# MCU.net
KiCad netlist of a schematic drawn in Altium Designer
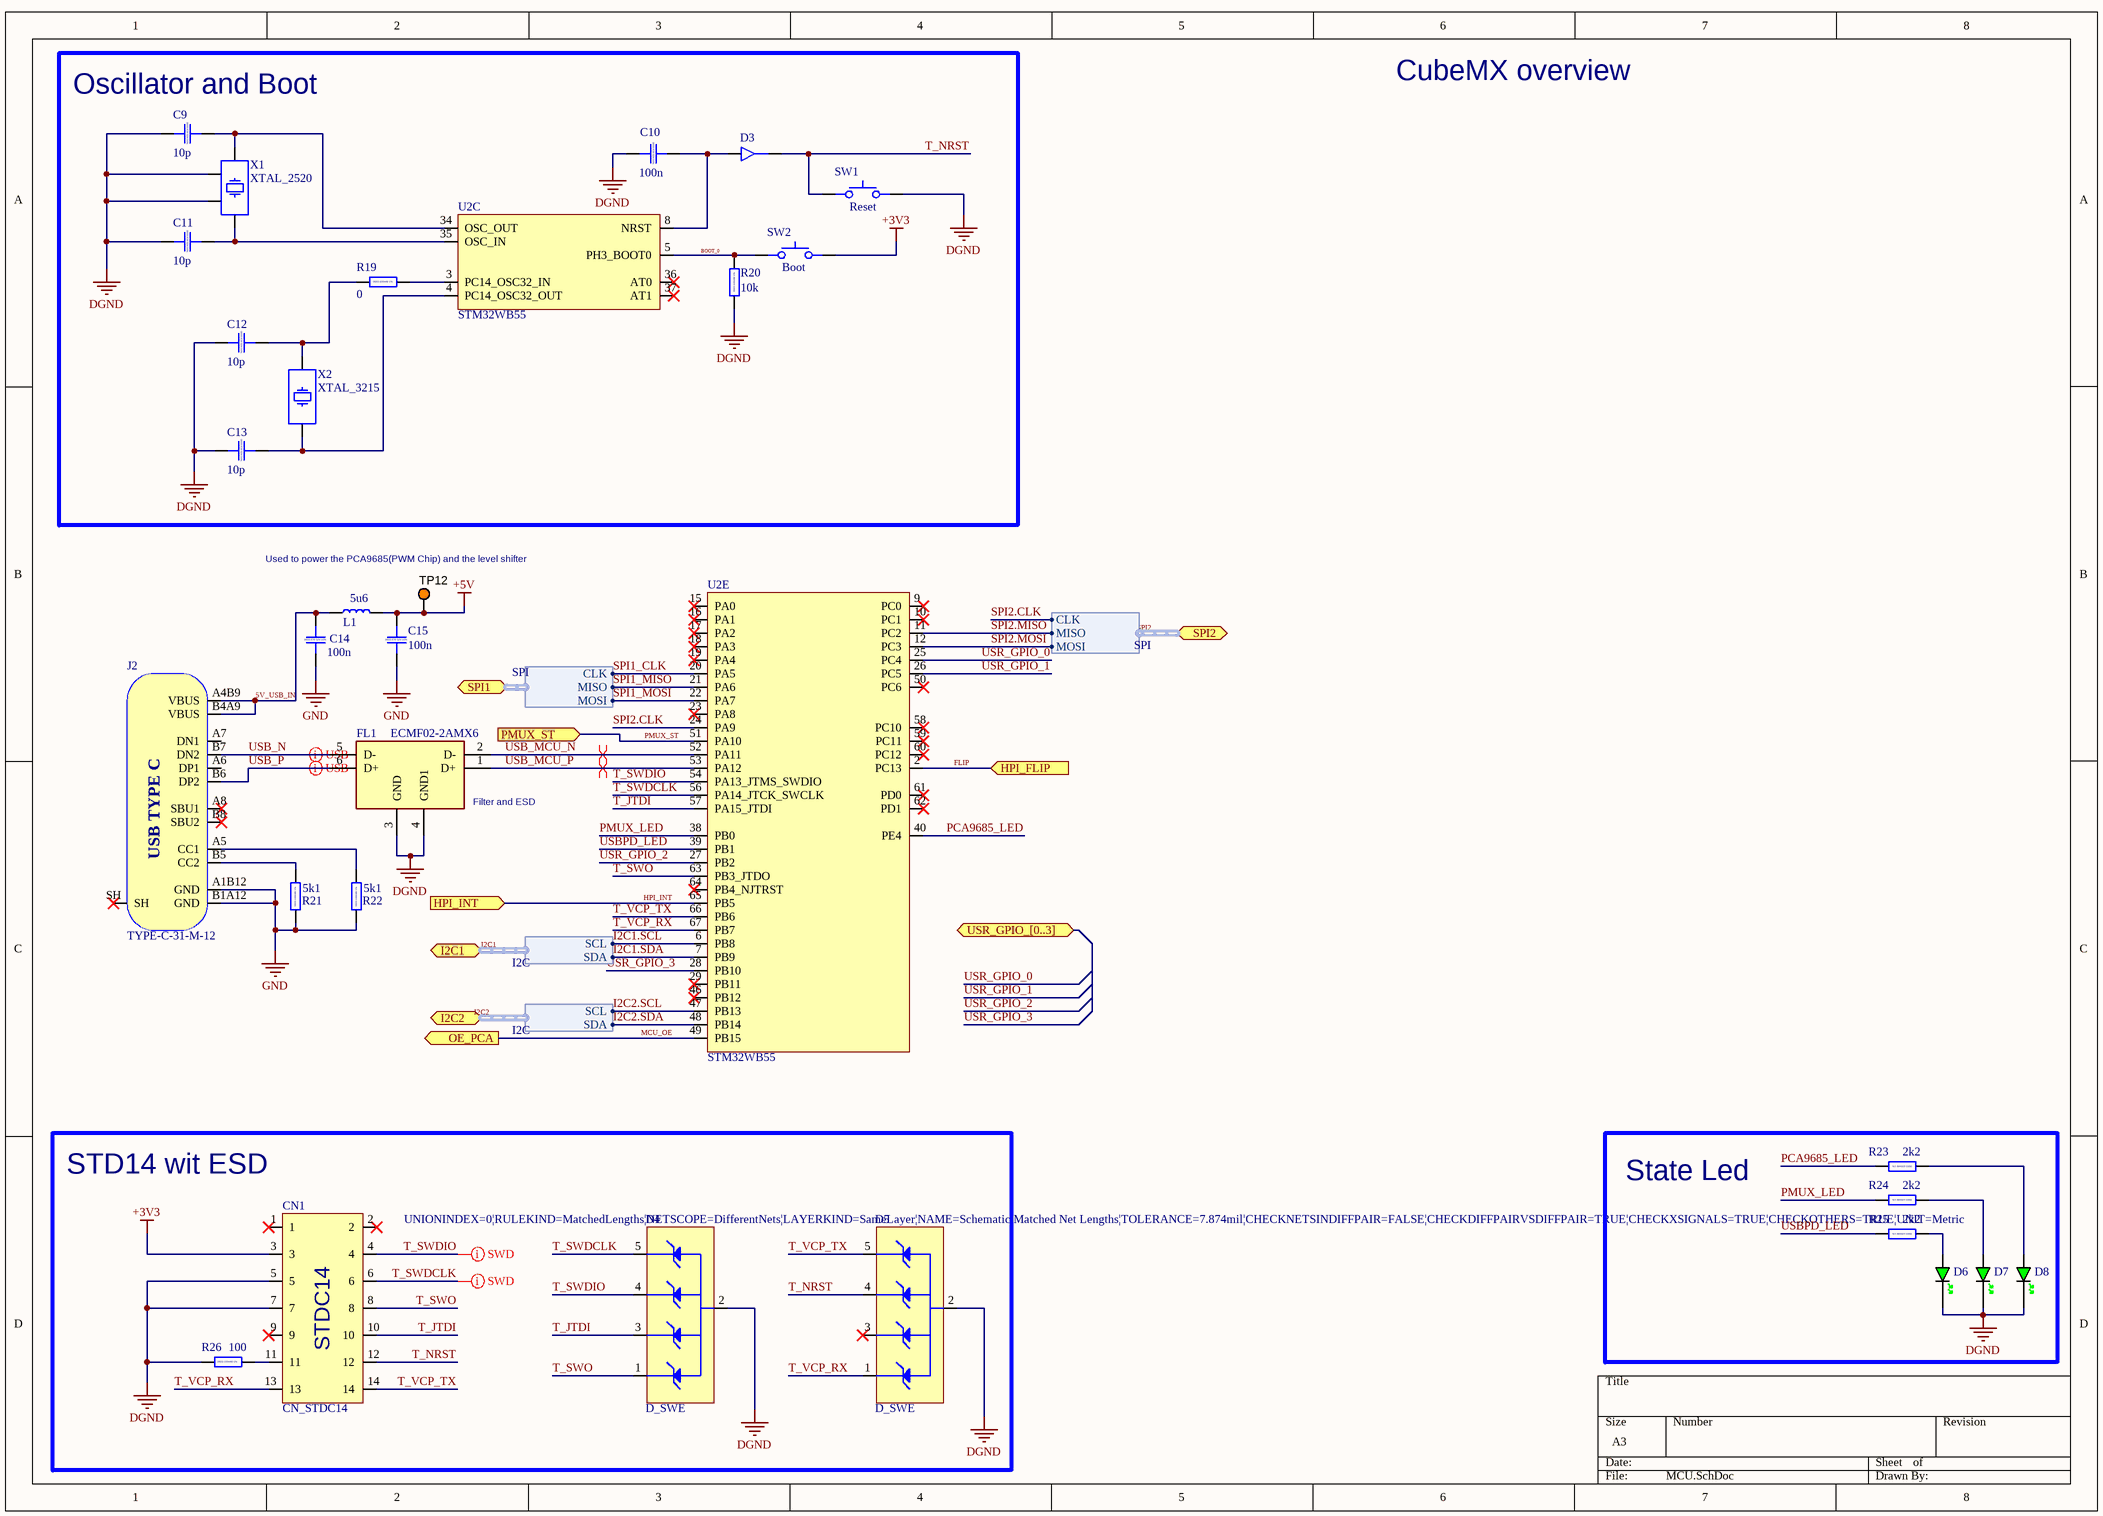
[diagram p0: MCU.SchDoc]

(export (version "E")
  (design (tool "Eeschema 10.0.6"))
  (components
    (comp (ref "C9")
      (value "10p")
      (footprint "CAP_0603")
      (description "Capacitor SMD 0603")
      (fields (field (name "SOURCE") "Schematic-Lib-PhilsLab.SchLib"))
      (libsource (lib "Leonhard Waibl") (part "CAP_EL_NP_5MM"))
    )
    (comp (ref "C10")
      (value "100n")
      (footprint "CAP_0603")
      (description "Capacitor SMD 0603")
      (fields (field (name "SOURCE") "Schematic-Lib-PhilsLab.SchLib"))
      (libsource (lib "Leonhard Waibl") (part "CAP_EL_NP_5MM"))
    )
    (comp (ref "C11")
      (value "10p")
      (footprint "CAP_0603")
      (description "Capacitor SMD 0603")
      (fields (field (name "SOURCE") "Schematic-Lib-PhilsLab.SchLib"))
      (libsource (lib "Leonhard Waibl") (part "CAP_EL_NP_5MM"))
    )
    (comp (ref "C12")
      (value "10p")
      (footprint "CAP_0603")
      (description "Capacitor SMD 0603")
      (fields (field (name "SOURCE") "Schematic-Lib-PhilsLab.SchLib"))
      (libsource (lib "Leonhard Waibl") (part "CAP_EL_NP_5MM"))
    )
    (comp (ref "C13")
      (value "10p")
      (footprint "CAP_0603")
      (description "Capacitor SMD 0603")
      (fields (field (name "SOURCE") "Schematic-Lib-PhilsLab.SchLib"))
      (libsource (lib "Leonhard Waibl") (part "CAP_EL_NP_5MM"))
    )
    (comp (ref "C14")
      (value "100n")
      (footprint "CAP_0603")
      (description "Capacitor SMD 0603")
      (fields (field (name "SOURCE") "Schematic-Lib-PhilsLab.SchLib"))
      (libsource (lib "Leonhard Waibl") (part "CAP_EL_NP_5MM"))
    )
    (comp (ref "C15")
      (value "100n")
      (footprint "CAP_0603")
      (description "Capacitor SMD 0603")
      (fields (field (name "SOURCE") "Schematic-Lib-PhilsLab.SchLib"))
      (libsource (lib "Leonhard Waibl") (part "CAP_EL_NP_5MM"))
    )
    (comp (ref "CN1")
      (value "CN_STDC14")
      (footprint "FTSH-107-01-F-DV-K-P-TR-Footprint-1")
      (libsource (lib "Leonhard Waibl") (part "CN_STDC14"))
    )
    (comp (ref "D3")
      (value "D_SOD_323")
      (footprint "SOD-323")
      (description "Diode SMD SOD-323")
      (fields (field (name "SOURCE") "Schematic-Lib-PhilsLab.SchLib"))
      (libsource (lib "Leonhard Waibl") (part "D_ZENER_SOD_323"))
    )
    (comp (ref "D4")
      (value "D_SWE")
      (footprint "SOT65P210X110-5N")
      (description "ESDALC6V1W5 Trans Voltage Suppressor Diode, 25W, Unidirectional, 4 Element, Silicon")
      (libsource (lib "Leonhard Waibl") (part "ESDALC6V1W5"))
    )
    (comp (ref "D5")
      (value "D_SWE")
      (footprint "SOT65P210X110-5N")
      (description "ESDALC6V1W5 Trans Voltage Suppressor Diode, 25W, Unidirectional, 4 Element, Silicon")
      (libsource (lib "Leonhard Waibl") (part "ESDALC6V1W5"))
    )
    (comp (ref "D6")
      (value "LED_0603_GREEN")
      (footprint "LED_0603_GREEN")
      (description "LED 0603 GREEN SMD")
      (fields (field (name "SOURCE") "Schematic-Lib-PhilsLab.SchLib"))
      (libsource (lib "Leonhard Waibl") (part "LED_0805_GREEN"))
    )
    (comp (ref "D7")
      (value "LED_0603_GREEN")
      (footprint "LED_0603_GREEN")
      (description "LED 0603 GREEN SMD")
      (fields (field (name "SOURCE") "Schematic-Lib-PhilsLab.SchLib"))
      (libsource (lib "Leonhard Waibl") (part "LED_0805_GREEN"))
    )
    (comp (ref "D8")
      (value "LED_0603_GREEN")
      (footprint "LED_0603_GREEN")
      (description "LED 0603 GREEN SMD")
      (fields (field (name "SOURCE") "Schematic-Lib-PhilsLab.SchLib"))
      (libsource (lib "Leonhard Waibl") (part "LED_0805_GREEN"))
    )
    (comp (ref "FL1")
      (value "ECMF02-2AMX6")
      (footprint "FP-QFN-6L-IPC_A")
      (description "Data Line Filter, 2 Function(s), 6 Pin(s), Plastic")
      (libsource (lib "Leonhard Waibl") (part "8feffc7f24acfb857157da90e949b57"))
    )
    (comp (ref "J2")
      (value "TYPE-C-31-M-12")
      (footprint "TYPE-C-31-M-12")
      (description "USB Type C Connector Horizontal SMT")
      (fields
        (field (name "MANUFACTURER") "Koren Hroparts")
        (field (name "SOURCE") "Schematic-Lib-PhilsLab.SchLib")
      )
      (libsource (lib "Leonhard Waibl") (part "TYPE-C-31-M-12"))
    )
    (comp (ref "L1")
      (value "5u6")
      (footprint "IND_0603")
      (description "Inductor SMD 0603")
      (fields (field (name "SOURCE") "Schematic-Lib-PhilsLab.SchLib"))
      (libsource (lib "Leonhard Waibl") (part "ASPI-0630HI-6R8M-T15"))
    )
    (comp (ref "R19")
      (value "0")
      (footprint "RES_0603")
      (description "Resistor 0603 100mW 1%")
      (fields (field (name "SOURCE") "Schematic-Lib-PhilsLab.SchLib"))
      (libsource (lib "Leonhard Waibl") (part "RES_5931"))
    )
    (comp (ref "R20")
      (value "10k")
      (footprint "RES_0603")
      (description "Resistor 0603 100mW 1%")
      (fields (field (name "SOURCE") "Schematic-Lib-PhilsLab.SchLib"))
      (libsource (lib "Leonhard Waibl") (part "RES_5931"))
    )
    (comp (ref "R21")
      (value "5k1")
      (footprint "RES_0603")
      (description "Resistor 0603 100mW 1%")
      (fields (field (name "SOURCE") "Schematic-Lib-PhilsLab.SchLib"))
      (libsource (lib "Leonhard Waibl") (part "RES_5931"))
    )
    (comp (ref "R22")
      (value "5k1")
      (footprint "RES_0603")
      (description "Resistor 0603 100mW 1%")
      (fields (field (name "SOURCE") "Schematic-Lib-PhilsLab.SchLib"))
      (libsource (lib "Leonhard Waibl") (part "RES_5931"))
    )
    (comp (ref "R23")
      (value "2k2")
      (footprint "RES_0603")
      (description "Resistor 0603 100mW 1%")
      (fields (field (name "SOURCE") "Schematic-Lib-PhilsLab.SchLib"))
      (libsource (lib "Leonhard Waibl") (part "RES_5931"))
    )
    (comp (ref "R24")
      (value "2k2")
      (footprint "RES_0603")
      (description "Resistor 0603 100mW 1%")
      (fields (field (name "SOURCE") "Schematic-Lib-PhilsLab.SchLib"))
      (libsource (lib "Leonhard Waibl") (part "RES_5931"))
    )
    (comp (ref "R25")
      (value "2k2")
      (footprint "RES_0603")
      (description "Resistor 0603 100mW 1%")
      (fields (field (name "SOURCE") "Schematic-Lib-PhilsLab.SchLib"))
      (libsource (lib "Leonhard Waibl") (part "RES_5931"))
    )
    (comp (ref "R26")
      (value "100")
      (footprint "RES_0603")
      (description "Resistor 0603 100mW 1%")
      (fields (field (name "SOURCE") "Schematic-Lib-PhilsLab.SchLib"))
      (libsource (lib "Leonhard Waibl") (part "RES_5931"))
    )
    (comp (ref "SW1")
      (value "Reset")
      (footprint "SKRPANE010")
      (description "Tactile Switch SMD SPST")
      (fields
        (field (name "MANUFACTURER PART NUMBER") "SKRPANE010")
        (field (name "MANUFACTURER") "Alps Alpine")
        (field (name "SOURCE") "Schematic-Lib-PhilsLab.SchLib")
      )
      (libsource (lib "Leonhard Waibl") (part "SKRPANE010"))
    )
    (comp (ref "SW2")
      (value "Boot")
      (footprint "SKRPANE010")
      (description "Tactile Switch SMD SPST")
      (fields
        (field (name "MANUFACTURER PART NUMBER") "SKRPANE010")
        (field (name "MANUFACTURER") "Alps Alpine")
        (field (name "SOURCE") "Schematic-Lib-PhilsLab.SchLib")
      )
      (libsource (lib "Leonhard Waibl") (part "SKRPANE010"))
    )
    (comp (ref "TP12")
      (value "5003")
      (footprint "KSTN-5003")
      (description "Test Point, Orange, Height 4.6 mm, Tail Length 3 mm, 1-Pin THD, RoHS")
      (fields (field (name "MANUFACTURER") "Keystone"))
      (libsource (lib "Leonhard Waibl") (part "TESTPOINT_ORANGE"))
    )
    (comp (ref "U2")
      (value "STM32WB55")
      (footprint "QFN40P800X800X100_HS-69N")
      (description "Multiprotocol wireless 32-bit MCU Arm®-based Cortex®-M4")
      (libsource (lib "Leonhard Waibl") (part "STM32WBxx_QFN68"))
    )
    (comp (ref "X1")
      (value "XTAL_2520")
      (footprint "XTAL_2520")
      (description "Crystal SMD 2520")
      (fields (field (name "SOURCE") "Schematic-Lib-PhilsLab.SchLib"))
      (libsource (lib "Leonhard Waibl") (part "TSX-3225_24.0000MF15X-AC"))
    )
    (comp (ref "X2")
      (value "XTAL_3215")
      (footprint "XTAL_3215-2")
      (description "Crystal SMD 3215")
      (fields (field (name "SOURCE") "Schematic-Lib-PhilsLab.SchLib"))
      (libsource (lib "Leonhard Waibl") (part "XTAL_3215"))
    )
  )
  (nets
    (net (code "5") (name "+3V3") (class "Default")
      (node (ref "CN1") (pin "3") (pinfunction "3_3") (pintype "passive"))
      (node (ref "SW2") (pin "34") (pintype "passive"))
    )
    (net (code "6") (name "+5V") (class "Default")
      (node (ref "C15") (pin "1") (pinfunction "1_1") (pintype "passive"))
      (node (ref "L1") (pin "2") (pinfunction "2_2") (pintype "passive"))
      (node (ref "TP12") (pin "1") (pinfunction "1_1") (pintype "passive"))
    )
    (net (code "7") (name "/5V_USB_IN") (class "Default")
      (node (ref "C14") (pin "1") (pinfunction "1_1") (pintype "passive"))
      (node (ref "J2") (pin "A4B9") (pinfunction "VBUS_A4B9") (pintype "power_in"))
      (node (ref "J2") (pin "B4A9") (pinfunction "VBUS_B4A9") (pintype "power_in"))
      (node (ref "L1") (pin "1") (pinfunction "1_1") (pintype "passive"))
    )
    (net (code "8") (name "/BOOT_0") (class "Default")
      (node (ref "R20") (pin "2") (pinfunction "2_2") (pintype "passive"))
      (node (ref "SW2") (pin "12") (pintype "passive"))
      (node (ref "U2") (pin "5") (pinfunction "PH3_BOOT0_5") (pintype "passive"))
    )
    (net (code "9") (name "/FLIP") (class "Default")
      (node (ref "U2") (pin "2") (pinfunction "PC13_2") (pintype "passive"))
    )
    (net (code "10") (name "/HPI_INT") (class "Default")
      (node (ref "U2") (pin "65") (pinfunction "PB5_65") (pintype "passive"))
    )
    (net (code "11") (name "/I2C1.SCL") (class "Default")
      (node (ref "U2") (pin "6") (pinfunction "PB8_6") (pintype "passive"))
    )
    (net (code "12") (name "/I2C1.SDA") (class "Default")
      (node (ref "U2") (pin "7") (pinfunction "PB9_7") (pintype "passive"))
    )
    (net (code "14") (name "/I2C2.SCL") (class "Default")
      (node (ref "U2") (pin "47") (pinfunction "PB13_47") (pintype "passive"))
    )
    (net (code "15") (name "/I2C2.SDA") (class "Default")
      (node (ref "U2") (pin "48") (pinfunction "PB14_48") (pintype "passive"))
    )
    (net (code "17") (name "/MCU_OE") (class "Default")
      (node (ref "U2") (pin "49") (pinfunction "PB15_49") (pintype "passive"))
    )
    (net (code "18") (name "/PCA9685_LED") (class "Default")
      (node (ref "R23") (pin "2") (pinfunction "2_2") (pintype "passive"))
      (node (ref "U2") (pin "40") (pinfunction "PE4_40") (pintype "passive"))
    )
    (net (code "19") (name "/PMUX_LED") (class "Default")
      (node (ref "R24") (pin "2") (pinfunction "2_2") (pintype "passive"))
      (node (ref "U2") (pin "38") (pinfunction "PB0_38") (pintype "passive"))
    )
    (net (code "20") (name "/PMUX_ST") (class "Default")
      (node (ref "U2") (pin "51") (pinfunction "PA10_51") (pintype "passive"))
    )
    (net (code "21") (name "/SPI1_CLK") (class "Default")
      (node (ref "U2") (pin "20") (pinfunction "PA5_20") (pintype "passive"))
    )
    (net (code "22") (name "/SPI1_MISO") (class "Default")
      (node (ref "U2") (pin "21") (pinfunction "PA6_21") (pintype "passive"))
    )
    (net (code "23") (name "/SPI1_MOSI") (class "Default")
      (node (ref "U2") (pin "22") (pinfunction "PA7_22") (pintype "passive"))
    )
    (net (code "24") (name "/SPI2.CLK") (class "Default")
      (node (ref "U2") (pin "24") (pinfunction "PA9_24") (pintype "passive"))
    )
    (net (code "25") (name "/SPI2.MISO") (class "Default")
      (node (ref "U2") (pin "11") (pinfunction "PC2_11") (pintype "passive"))
    )
    (net (code "26") (name "/SPI2.MOSI") (class "Default")
      (node (ref "U2") (pin "12") (pinfunction "PC3_12") (pintype "passive"))
    )
    (net (code "28") (name "/T_JTDI") (class "Default")
      (node (ref "CN1") (pin "10") (pinfunction "10_10") (pintype "passive"))
      (node (ref "D4") (pin "3") (pinfunction "3_3") (pintype "passive"))
      (node (ref "U2") (pin "57") (pinfunction "PA15_JTDI_57") (pintype "passive"))
    )
    (net (code "29") (name "/T_NRST") (class "Default")
      (node (ref "CN1") (pin "12") (pinfunction "12_12") (pintype "passive"))
      (node (ref "D3") (pin "K") (pinfunction "K_K") (pintype "passive"))
      (node (ref "D5") (pin "4") (pinfunction "4_4") (pintype "passive"))
      (node (ref "SW1") (pin "12") (pintype "passive"))
    )
    (net (code "30") (name "/T_SWDCLK") (class "Default")
      (node (ref "CN1") (pin "6") (pinfunction "6_6") (pintype "passive"))
      (node (ref "D4") (pin "5") (pinfunction "5_5") (pintype "passive"))
      (node (ref "U2") (pin "56") (pinfunction "PA14_JTCK_SWCLK_56") (pintype "passive"))
    )
    (net (code "31") (name "/T_SWDIO") (class "Default")
      (node (ref "CN1") (pin "4") (pinfunction "4_4") (pintype "passive"))
      (node (ref "D4") (pin "4") (pinfunction "4_4") (pintype "passive"))
      (node (ref "U2") (pin "54") (pinfunction "PA13_JTMS_SWDIO_54") (pintype "passive"))
    )
    (net (code "32") (name "/T_SWO") (class "Default")
      (node (ref "CN1") (pin "8") (pinfunction "8_8") (pintype "passive"))
      (node (ref "D4") (pin "1") (pinfunction "1_1") (pintype "passive"))
      (node (ref "U2") (pin "63") (pinfunction "PB3_JTDO_63") (pintype "passive"))
    )
    (net (code "33") (name "/T_VCP_RX") (class "Default")
      (node (ref "CN1") (pin "13") (pinfunction "13_13") (pintype "passive"))
      (node (ref "D5") (pin "1") (pinfunction "1_1") (pintype "passive"))
      (node (ref "U2") (pin "67") (pinfunction "PB7_67") (pintype "passive"))
    )
    (net (code "34") (name "/T_VCP_TX") (class "Default")
      (node (ref "CN1") (pin "14") (pinfunction "14_14") (pintype "passive"))
      (node (ref "D5") (pin "5") (pinfunction "5_5") (pintype "passive"))
      (node (ref "U2") (pin "66") (pinfunction "PB6_66") (pintype "passive"))
    )
    (net (code "35") (name "/USBPD_LED") (class "Default")
      (node (ref "R25") (pin "2") (pinfunction "2_2") (pintype "passive"))
      (node (ref "U2") (pin "39") (pinfunction "PB1_39") (pintype "passive"))
    )
    (net (code "36") (name "/USB_MCU_N") (class "Default")
      (node (ref "FL1") (pin "2") (pinfunction "D-_2") (pintype "passive"))
      (node (ref "U2") (pin "52") (pinfunction "PA11_52") (pintype "passive"))
    )
    (net (code "37") (name "/USB_MCU_P") (class "Default")
      (node (ref "FL1") (pin "1") (pinfunction "D+_1") (pintype "passive"))
      (node (ref "U2") (pin "53") (pinfunction "PA12_53") (pintype "passive"))
    )
    (net (code "38") (name "/USB_N") (class "Default")
      (node (ref "FL1") (pin "5") (pinfunction "D-_5") (pintype "passive"))
      (node (ref "J2") (pin "B7") (pinfunction "DN2_B7") (pintype "bidirectional"))
    )
    (net (code "39") (name "/USB_P") (class "Default")
      (node (ref "FL1") (pin "6") (pinfunction "D+_6") (pintype "passive"))
      (node (ref "J2") (pin "B6") (pinfunction "DP2_B6") (pintype "bidirectional"))
    )
    (net (code "40") (name "/USR_GPIO_0") (class "Default")
      (node (ref "U2") (pin "25") (pinfunction "PC4_25") (pintype "passive"))
    )
    (net (code "41") (name "/USR_GPIO_1") (class "Default")
      (node (ref "U2") (pin "26") (pinfunction "PC5_26") (pintype "passive"))
    )
    (net (code "42") (name "/USR_GPIO_2") (class "Default")
      (node (ref "U2") (pin "27") (pinfunction "PB2_27") (pintype "passive"))
    )
    (net (code "43") (name "/USR_GPIO_3") (class "Default")
      (node (ref "U2") (pin "28") (pinfunction "PB10_28") (pintype "passive"))
    )
    (net (code "46") (name "DGND") (class "Default")
      (node (ref "C10") (pin "2") (pinfunction "2_2") (pintype "passive"))
      (node (ref "C11") (pin "2") (pinfunction "2_2") (pintype "passive"))
      (node (ref "C12") (pin "2") (pinfunction "2_2") (pintype "passive"))
      (node (ref "C13") (pin "2") (pinfunction "2_2") (pintype "passive"))
      (node (ref "C9") (pin "2") (pinfunction "2_2") (pintype "passive"))
      (node (ref "CN1") (pin "5") (pinfunction "5_5") (pintype "passive"))
      (node (ref "CN1") (pin "7") (pinfunction "7_7") (pintype "passive"))
      (node (ref "D4") (pin "2") (pinfunction "2_2") (pintype "passive"))
      (node (ref "D5") (pin "2") (pinfunction "2_2") (pintype "passive"))
      (node (ref "D6") (pin "K") (pinfunction "K_K") (pintype "passive"))
      (node (ref "D7") (pin "K") (pinfunction "K_K") (pintype "passive"))
      (node (ref "D8") (pin "K") (pinfunction "K_K") (pintype "passive"))
      (node (ref "FL1") (pin "3") (pinfunction "GND_3") (pintype "power_in"))
      (node (ref "FL1") (pin "4") (pinfunction "GND1_4") (pintype "power_in"))
      (node (ref "R20") (pin "1") (pinfunction "1_1") (pintype "passive"))
      (node (ref "R26") (pin "1") (pinfunction "1_1") (pintype "passive"))
      (node (ref "SW1") (pin "34") (pintype "passive"))
      (node (ref "X1") (pin "2") (pinfunction "2_2") (pintype "passive"))
      (node (ref "X1") (pin "4") (pinfunction "4_4") (pintype "passive"))
    )
    (net (code "47") (name "GND") (class "Default")
      (node (ref "C14") (pin "2") (pinfunction "2_2") (pintype "passive"))
      (node (ref "C15") (pin "2") (pinfunction "2_2") (pintype "passive"))
      (node (ref "J2") (pin "A1B12") (pinfunction "GND_A1B12") (pintype "power_in"))
      (node (ref "J2") (pin "B1A12") (pinfunction "GND_B1A12") (pintype "power_in"))
      (node (ref "R21") (pin "1") (pinfunction "1_1") (pintype "passive"))
      (node (ref "R22") (pin "1") (pinfunction "1_1") (pintype "passive"))
    )
    (net (code "48") (name "Net-(C12-Pad1)") (class "Default")
      (node (ref "C12") (pin "1") (pinfunction "1_1") (pintype "passive"))
      (node (ref "R19") (pin "1") (pinfunction "1_1") (pintype "passive"))
      (node (ref "X2") (pin "2") (pinfunction "2_2") (pintype "passive"))
    )
    (net (code "49") (name "Net-(CN1-Pad11)") (class "Default")
      (node (ref "CN1") (pin "11") (pinfunction "11_11") (pintype "passive"))
      (node (ref "R26") (pin "2") (pinfunction "2_2") (pintype "passive"))
    )
    (net (code "50") (name "Net-(D6-PadA)") (class "Default")
      (node (ref "D6") (pin "A") (pinfunction "A_A") (pintype "passive"))
      (node (ref "R25") (pin "1") (pinfunction "1_1") (pintype "passive"))
    )
    (net (code "51") (name "Net-(D7-PadA)") (class "Default")
      (node (ref "D7") (pin "A") (pinfunction "A_A") (pintype "passive"))
      (node (ref "R24") (pin "1") (pinfunction "1_1") (pintype "passive"))
    )
    (net (code "52") (name "Net-(D8-PadA)") (class "Default")
      (node (ref "D8") (pin "A") (pinfunction "A_A") (pintype "passive"))
      (node (ref "R23") (pin "1") (pinfunction "1_1") (pintype "passive"))
    )
    (net (code "53") (name "Net-(J2-CC1)") (class "Default")
      (node (ref "J2") (pin "A5") (pinfunction "CC1_A5") (pintype "passive"))
      (node (ref "R22") (pin "2") (pinfunction "2_2") (pintype "passive"))
    )
    (net (code "54") (name "Net-(J2-CC2)") (class "Default")
      (node (ref "J2") (pin "B5") (pinfunction "CC2_B5") (pintype "tri_state"))
      (node (ref "R21") (pin "2") (pinfunction "2_2") (pintype "passive"))
    )
    (net (code "55") (name "Net-(U2C-NRST)") (class "Default")
      (node (ref "C10") (pin "1") (pinfunction "1_1") (pintype "passive"))
      (node (ref "D3") (pin "A") (pinfunction "A_A") (pintype "passive"))
      (node (ref "U2") (pin "8") (pinfunction "NRST_8") (pintype "passive"))
    )
    (net (code "56") (name "Net-(U2C-OSC_IN)") (class "Default")
      (node (ref "C11") (pin "1") (pinfunction "1_1") (pintype "passive"))
      (node (ref "U2") (pin "35") (pinfunction "OSC_IN_35") (pintype "passive"))
      (node (ref "X1") (pin "3") (pinfunction "3_3") (pintype "passive"))
    )
    (net (code "57") (name "Net-(U2C-OSC_OUT)") (class "Default")
      (node (ref "C9") (pin "1") (pinfunction "1_1") (pintype "passive"))
      (node (ref "U2") (pin "34") (pinfunction "OSC_OUT_34") (pintype "passive"))
      (node (ref "X1") (pin "1") (pinfunction "1_1") (pintype "passive"))
    )
    (net (code "58") (name "Net-(U2C-PC14_OSC32_IN)") (class "Default")
      (node (ref "R19") (pin "2") (pinfunction "2_2") (pintype "passive"))
      (node (ref "U2") (pin "3") (pinfunction "PC14_OSC32_IN_3") (pintype "passive"))
    )
    (net (code "59") (name "Net-(U2C-PC14_OSC32_OUT)") (class "Default")
      (node (ref "C13") (pin "1") (pinfunction "1_1") (pintype "passive"))
      (node (ref "U2") (pin "4") (pinfunction "PC14_OSC32_OUT_4") (pintype "passive"))
      (node (ref "X2") (pin "1") (pinfunction "1_1") (pintype "passive"))
    )
    (net (code "60") (name "unconnected-(CN1-Pad1)") (class "Default")
      (node (ref "CN1") (pin "1") (pinfunction "1_1") (pintype "passive+no_connect"))
    )
    (net (code "61") (name "unconnected-(CN1-Pad2)") (class "Default")
      (node (ref "CN1") (pin "2") (pinfunction "2_2") (pintype "passive+no_connect"))
    )
    (net (code "62") (name "unconnected-(CN1-Pad9)") (class "Default")
      (node (ref "CN1") (pin "9") (pinfunction "9_9") (pintype "passive+no_connect"))
    )
    (net (code "63") (name "unconnected-(D5-Pad3)") (class "Default")
      (node (ref "D5") (pin "3") (pinfunction "3_3") (pintype "passive+no_connect"))
    )
    (net (code "64") (name "unconnected-(J2-DN1-PadA7)") (class "Default")
      (node (ref "J2") (pin "A7") (pinfunction "DN1_A7") (pintype "bidirectional"))
    )
    (net (code "65") (name "unconnected-(J2-DP1-PadA6)") (class "Default")
      (node (ref "J2") (pin "A6") (pinfunction "DP1_A6") (pintype "bidirectional"))
    )
    (net (code "66") (name "unconnected-(J2-PadSH)") (class "Default")
      (node (ref "J2") (pin "SH") (pinfunction "SH_SH") (pintype "power_in+no_connect"))
    )
    (net (code "67") (name "unconnected-(J2-SBU1-PadA8)") (class "Default")
      (node (ref "J2") (pin "A8") (pinfunction "SBU1_A8") (pintype "bidirectional+no_connect"))
    )
    (net (code "68") (name "unconnected-(J2-SBU2-PadB8)") (class "Default")
      (node (ref "J2") (pin "B8") (pinfunction "SBU2_B8") (pintype "bidirectional+no_connect"))
    )
    (net (code "69") (name "unconnected-(U2C-AT0-Pad36)") (class "Default")
      (node (ref "U2") (pin "36") (pinfunction "AT0_36") (pintype "passive+no_connect"))
    )
    (net (code "70") (name "unconnected-(U2C-AT1-Pad37)") (class "Default")
      (node (ref "U2") (pin "37") (pinfunction "AT1_37") (pintype "passive+no_connect"))
    )
    (net (code "71") (name "unconnected-(U2E-PA0-Pad15)") (class "Default")
      (node (ref "U2") (pin "15") (pinfunction "PA0_15") (pintype "passive+no_connect"))
    )
    (net (code "72") (name "unconnected-(U2E-PA1-Pad16)") (class "Default")
      (node (ref "U2") (pin "16") (pinfunction "PA1_16") (pintype "passive+no_connect"))
    )
    (net (code "73") (name "unconnected-(U2E-PA2-Pad17)") (class "Default")
      (node (ref "U2") (pin "17") (pinfunction "PA2_17") (pintype "passive+no_connect"))
    )
    (net (code "74") (name "unconnected-(U2E-PA3-Pad18)") (class "Default")
      (node (ref "U2") (pin "18") (pinfunction "PA3_18") (pintype "passive+no_connect"))
    )
    (net (code "75") (name "unconnected-(U2E-PA4-Pad19)") (class "Default")
      (node (ref "U2") (pin "19") (pinfunction "PA4_19") (pintype "passive+no_connect"))
    )
    (net (code "76") (name "unconnected-(U2E-PA8-Pad23)") (class "Default")
      (node (ref "U2") (pin "23") (pinfunction "PA8_23") (pintype "passive+no_connect"))
    )
    (net (code "77") (name "unconnected-(U2E-PB4_NJTRST-Pad64)") (class "Default")
      (node (ref "U2") (pin "64") (pinfunction "PB4_NJTRST_64") (pintype "passive+no_connect"))
    )
    (net (code "78") (name "unconnected-(U2E-PB11-Pad29)") (class "Default")
      (node (ref "U2") (pin "29") (pinfunction "PB11_29") (pintype "passive+no_connect"))
    )
    (net (code "79") (name "unconnected-(U2E-PB12-Pad46)") (class "Default")
      (node (ref "U2") (pin "46") (pinfunction "PB12_46") (pintype "passive+no_connect"))
    )
    (net (code "80") (name "unconnected-(U2E-PC0-Pad9)") (class "Default")
      (node (ref "U2") (pin "9") (pinfunction "PC0_9") (pintype "passive+no_connect"))
    )
    (net (code "81") (name "unconnected-(U2E-PC1-Pad10)") (class "Default")
      (node (ref "U2") (pin "10") (pinfunction "PC1_10") (pintype "passive+no_connect"))
    )
    (net (code "82") (name "unconnected-(U2E-PC6-Pad50)") (class "Default")
      (node (ref "U2") (pin "50") (pinfunction "PC6_50") (pintype "passive+no_connect"))
    )
    (net (code "83") (name "unconnected-(U2E-PC10-Pad58)") (class "Default")
      (node (ref "U2") (pin "58") (pinfunction "PC10_58") (pintype "passive+no_connect"))
    )
    (net (code "84") (name "unconnected-(U2E-PC11-Pad59)") (class "Default")
      (node (ref "U2") (pin "59") (pinfunction "PC11_59") (pintype "passive+no_connect"))
    )
    (net (code "85") (name "unconnected-(U2E-PC12-Pad60)") (class "Default")
      (node (ref "U2") (pin "60") (pinfunction "PC12_60") (pintype "passive+no_connect"))
    )
    (net (code "86") (name "unconnected-(U2E-PD0-Pad61)") (class "Default")
      (node (ref "U2") (pin "61") (pinfunction "PD0_61") (pintype "passive+no_connect"))
    )
    (net (code "87") (name "unconnected-(U2E-PD1-Pad62)") (class "Default")
      (node (ref "U2") (pin "62") (pinfunction "PD1_62") (pintype "passive+no_connect"))
    )
  )
)
